# ESP32.net
KiCad netlist of a schematic drawn in Altium Designer
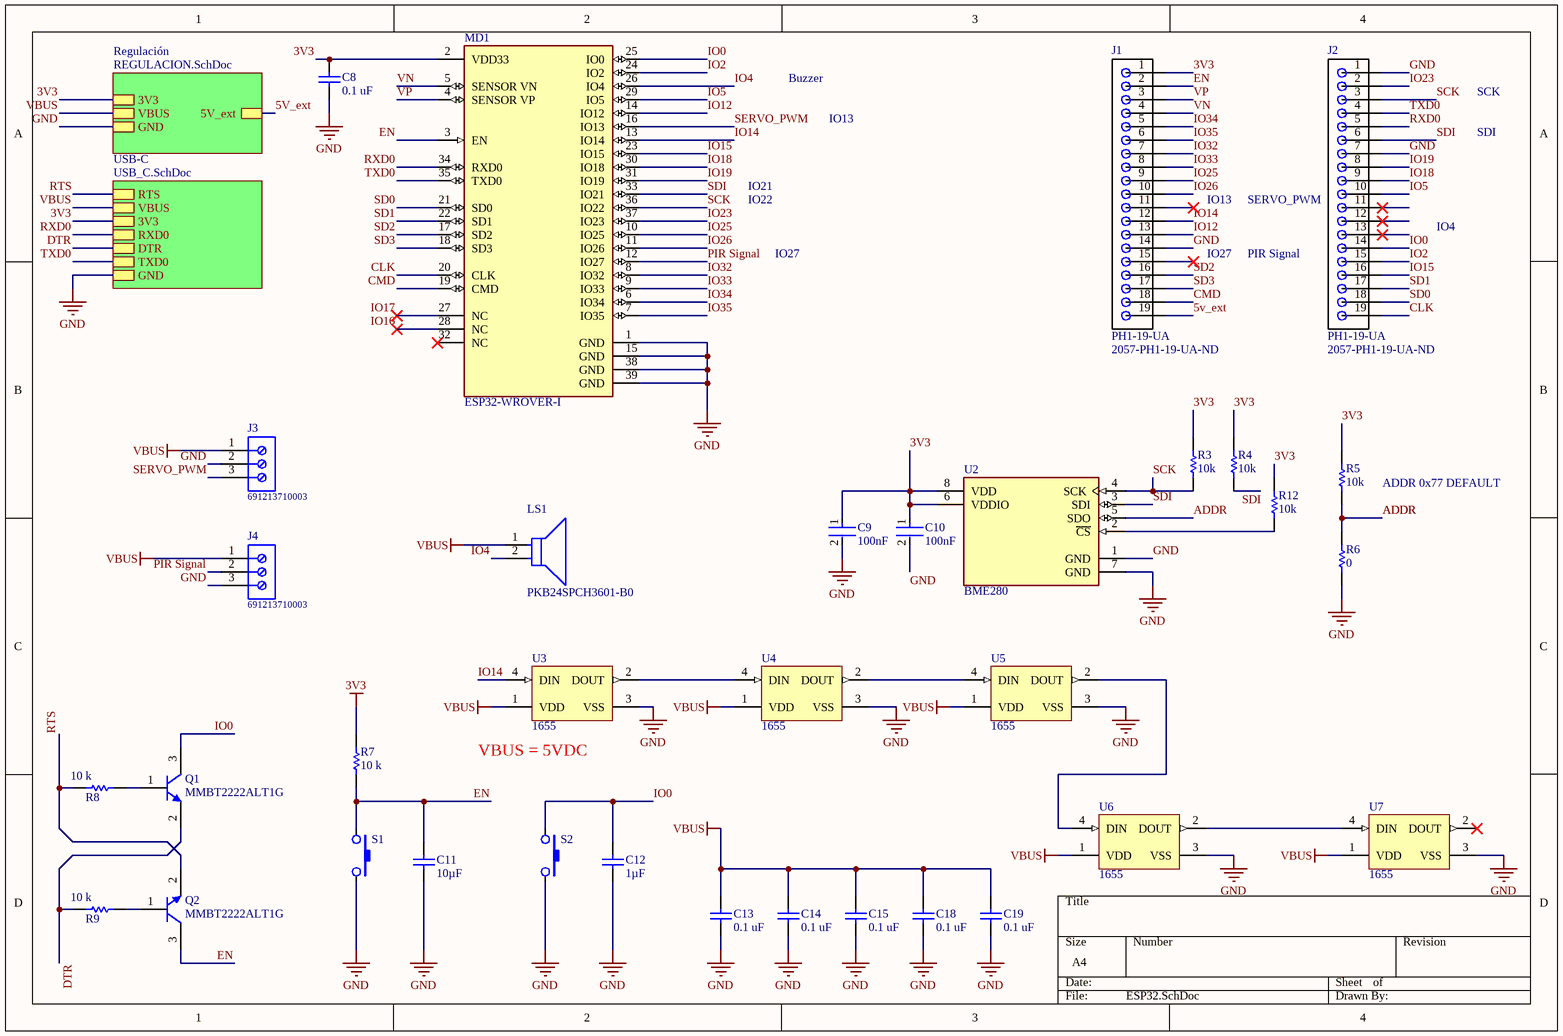
[diagram p0: ESP32.SchDoc]

(export (version "E")
  (design (tool "Eeschema 10.0.6"))
  (components
    (comp (ref "C8")
      (value "0.1 uF")
      (footprint "CAPC2013X94X50ML20T25")
      (description "Chip Capacitor, Ceramic, 0.1 uF, 10%, 50 V, 0805, RoHS, Tape and Reel")
      (fields (field (name "MANUFACTURER") "AVX"))
      (libsource (lib "Altium Content Vault") (part "CAP-NP-2"))
    )
    (comp (ref "C9")
      (value "100nF")
      (footprint "FP-C0805C-DN-MFG")
      (description "CAP CER 0.1UF 50V X7R 0805 C0805C104K5RACTU")
      (fields
        (field (name "MANUFACTURER PART NUMBER") "C0805C104K5RACTU")
        (field (name "MANUFACTURER") "KEMET")
      )
      (libsource (lib "Altium Content Vault") (part "b4654b650e69147ec39a6b967a45e02"))
    )
    (comp (ref "C10")
      (value "100nF")
      (footprint "FP-C0805C-DN-MFG")
      (description "CAP CER 0.1UF 50V X7R 0805 C0805C104K5RACTU")
      (fields
        (field (name "MANUFACTURER PART NUMBER") "C0805C104K5RACTU")
        (field (name "MANUFACTURER") "KEMET")
      )
      (libsource (lib "Altium Content Vault") (part "b4654b650e69147ec39a6b967a45e02"))
    )
    (comp (ref "C11")
      (value "10µF")
      (footprint "CAPC2013X145X50ML20T25")
      (description "1µF ±10% 16V Ceramic Capacitor X7R 0805 (2012 Metric)")
      (fields (field (name "MANUFACTURER") "Kemet") (field (name "PART NUMBER") "C0805C105K4RAC7800"))
      (libsource (lib "Altium Content Vault") (part "CAP"))
    )
    (comp (ref "C12")
      (value "1µF")
      (footprint "CAPC2013X145X50ML20T25")
      (description "1µF ±10% 16V Ceramic Capacitor X7R 0805 (2012 Metric)")
      (fields (field (name "MANUFACTURER") "Kemet") (field (name "PART NUMBER") "C0805C105K4RAC7800"))
      (libsource (lib "Altium Content Vault") (part "CAP"))
    )
    (comp (ref "C13")
      (value "0.1 uF")
      (footprint "CAPC2013X94X50ML20T25")
      (description "Chip Capacitor, Ceramic, 0.1 uF, 10%, 50 V, 0805, RoHS, Tape and Reel")
      (fields (field (name "MANUFACTURER") "AVX"))
      (libsource (lib "Altium Content Vault") (part "CAP-NP-2"))
    )
    (comp (ref "C14")
      (value "0.1 uF")
      (footprint "CAPC2013X94X50ML20T25")
      (description "Chip Capacitor, Ceramic, 0.1 uF, 10%, 50 V, 0805, RoHS, Tape and Reel")
      (fields (field (name "MANUFACTURER") "AVX"))
      (libsource (lib "Altium Content Vault") (part "CAP-NP-2"))
    )
    (comp (ref "C15")
      (value "0.1 uF")
      (footprint "CAPC2013X94X50ML20T25")
      (description "Chip Capacitor, Ceramic, 0.1 uF, 10%, 50 V, 0805, RoHS, Tape and Reel")
      (fields (field (name "MANUFACTURER") "AVX"))
      (libsource (lib "Altium Content Vault") (part "CAP-NP-2"))
    )
    (comp (ref "C18")
      (value "0.1 uF")
      (footprint "CAPC2013X94X50ML20T25")
      (description "Chip Capacitor, Ceramic, 0.1 uF, 10%, 50 V, 0805, RoHS, Tape and Reel")
      (fields (field (name "MANUFACTURER") "AVX"))
      (libsource (lib "Altium Content Vault") (part "CAP-NP-2"))
    )
    (comp (ref "C19")
      (value "0.1 uF")
      (footprint "CAPC2013X94X50ML20T25")
      (description "Chip Capacitor, Ceramic, 0.1 uF, 10%, 50 V, 0805, RoHS, Tape and Reel")
      (fields (field (name "MANUFACTURER") "AVX"))
      (libsource (lib "Altium Content Vault") (part "CAP-NP-2"))
    )
    (comp (ref "J1")
      (value "PH1-19-UA")
      (footprint "PH1-19-UA")
      (description "Connector Header Through Hole 19 position 0.100\" (2.54mm)")
      (fields (field (name "SUPPLIER PART NUMBER 1") "2057-PH1-19-UA-ND"))
      (libsource (lib "Isidro_Library") (part "PH1-19-UA"))
    )
    (comp (ref "J2")
      (value "PH1-19-UA")
      (footprint "PH1-19-UA")
      (description "Connector Header Through Hole 19 position 0.100\" (2.54mm)")
      (fields (field (name "SUPPLIER PART NUMBER 1") "2057-PH1-19-UA-ND"))
      (libsource (lib "Isidro_Library") (part "PH1-19-UA"))
    )
    (comp (ref "J3")
      (value "691213710003")
      (footprint "691213710003")
      (description "Serie 213 - 5.00 mm Horizontal Entry Modular with RisingCage Clamp WR-TBL, 3 pin")
      (fields (field (name "MANUFACTURER") "Wurth Elektronik") (field (name "PUBLISHER") "WurthElektronik"))
      (libsource (lib "Altium Content Vault") (part "WE-CN-1P-F-TB3"))
    )
    (comp (ref "J4")
      (value "691213710003")
      (footprint "691213710003")
      (description "Serie 213 - 5.00 mm Horizontal Entry Modular with RisingCage Clamp WR-TBL, 3 pin")
      (fields (field (name "MANUFACTURER") "Wurth Elektronik") (field (name "PUBLISHER") "WurthElektronik"))
      (libsource (lib "Altium Content Vault") (part "WE-CN-1P-F-TB3"))
    )
    (comp (ref "LS1")
      (value "PKB24SPCH3601-B0")
      (footprint "FP-PKB24SPCH3601-B0-MFG")
      (description "AUDIO PIEZO TRANSDUCER 3-15V TH")
      (libsource (lib "Altium Content Vault") (part "1973c4b650225fd2ddacaff6b763965"))
    )
    (comp (ref "MD1")
      (value "ESP32-WROVER-I")
      (footprint "FP-ESP32-WROVER-I-MFG")
      (description "SMD MODULE, ESP32-D0WDQ6, 32MBIT")
      (fields
        (field (name "MANUFACTURER") "Espressif")
        (field (name "OCTOPART") "https://octopart.com/esp32-wrover-i-espressif+systems-89171349")
      )
      (libsource (lib "Altium Content Vault") (part "cbbb37af8bcfe61dfd46ac9418f0340"))
    )
    (comp (ref "Q1")
      (value "MMBT2222ALT1G")
      (footprint "ONSC-SOT-23-3-318-08_V")
      (description "General Purpose Transistor, NPN Silicon, 3-Pin SOT-23, Pb-Free, Tape and Reel")
      (fields (field (name "MANUFACTURER") "On Semiconductor"))
      (libsource (lib "Altium Content Vault") (part "ONSC-NPN-B1E2C3-3"))
    )
    (comp (ref "Q2")
      (value "MMBT2222ALT1G")
      (footprint "ONSC-SOT-23-3-318-08_V")
      (description "General Purpose Transistor, NPN Silicon, 3-Pin SOT-23, Pb-Free, Tape and Reel")
      (fields (field (name "MANUFACTURER") "On Semiconductor"))
      (libsource (lib "Altium Content Vault") (part "ONSC-NPN-B1E2C3-3"))
    )
    (comp (ref "R3")
      (value "10k")
      (footprint "RESC2013X60X40LL20T25_A")
      (fields (field (name "TOLERANCE") "0.1%") (field (name "MANUFACTURER") "Panasonic"))
      (libsource (lib "Altium Content Vault") (part "RES-2"))
    )
    (comp (ref "R4")
      (value "10k")
      (footprint "RESC2013X60X40LL20T25_A")
      (fields (field (name "TOLERANCE") "0.1%") (field (name "MANUFACTURER") "Panasonic"))
      (libsource (lib "Altium Content Vault") (part "RES-2"))
    )
    (comp (ref "R5")
      (value "10k")
      (footprint "RESC2013X60X40LL20T25_A")
      (fields (field (name "TOLERANCE") "0.1%") (field (name "MANUFACTURER") "Panasonic"))
      (libsource (lib "Altium Content Vault") (part "RES-2"))
    )
    (comp (ref "R6")
      (value "0")
      (footprint "RESC2013X60X40LL20T25_A")
      (fields (field (name "TOLERANCE") "0.1%") (field (name "MANUFACTURER") "Panasonic"))
      (libsource (lib "Altium Content Vault") (part "RES-2"))
    )
    (comp (ref "R7")
      (value "10 k")
      (footprint "RESC2013X60X30ML20T20")
      (fields (field (name "PART NUMBER") "RK73B2ATTD103J") (field (name "MANUFACTURER") "KOA Speer"))
      (libsource (lib "Altium Content Vault") (part "RES"))
    )
    (comp (ref "R8")
      (value "10 k")
      (footprint "RESC2013X60X30ML20T20")
      (fields (field (name "PART NUMBER") "RK73B2ATTD103J") (field (name "MANUFACTURER") "KOA Speer"))
      (libsource (lib "Altium Content Vault") (part "RES"))
    )
    (comp (ref "R9")
      (value "10 k")
      (footprint "RESC2013X60X30ML20T20")
      (fields (field (name "PART NUMBER") "RK73B2ATTD103J") (field (name "MANUFACTURER") "KOA Speer"))
      (libsource (lib "Altium Content Vault") (part "RES"))
    )
    (comp (ref "R12")
      (value "10k")
      (footprint "RESC2013X60X40LL20T25_A")
      (fields (field (name "TOLERANCE") "0.1%") (field (name "MANUFACTURER") "Panasonic"))
      (libsource (lib "Altium Content Vault") (part "RES-2"))
    )
    (comp (ref "S1")
      (value "PTS820J25MSMTRLFS")
      (footprint "SMT_SW_PTS_820")
      (libsource (lib "SnapEDAsch") (part "PTS820J25MSMTRLFS"))
    )
    (comp (ref "S2")
      (value "IO0")
      (footprint "SMT_SW_PTS_820")
      (libsource (lib "SnapEDAsch") (part "PTS820J25MSMTRLFS"))
    )
    (comp (ref "U2")
      (value "BME280")
      (footprint "FP-BME280-MFG")
      (description "SENSOR PRESSURE HUMIDITY TEMP")
      (libsource (lib "Altium Content Vault") (part "d58e2f6669bc67e6a2bc6a28610ca79"))
    )
    (comp (ref "U3")
      (value "1655")
      (footprint "ADA-RGB-1655_V")
      (fields (field (name "MANUFACTURER") "Adafruit-Industries-LLC"))
      (libsource (lib "Altium Content Vault") (part "ADA-RGB-1655-4"))
    )
    (comp (ref "U4")
      (value "1655")
      (footprint "ADA-RGB-1655_V")
      (fields (field (name "MANUFACTURER") "Adafruit-Industries-LLC"))
      (libsource (lib "Altium Content Vault") (part "ADA-RGB-1655-4"))
    )
    (comp (ref "U5")
      (value "1655")
      (footprint "ADA-RGB-1655_V")
      (fields (field (name "MANUFACTURER") "Adafruit-Industries-LLC"))
      (libsource (lib "Altium Content Vault") (part "ADA-RGB-1655-4"))
    )
    (comp (ref "U6")
      (value "1655")
      (footprint "ADA-RGB-1655_V")
      (fields (field (name "MANUFACTURER") "Adafruit-Industries-LLC"))
      (libsource (lib "Altium Content Vault") (part "ADA-RGB-1655-4"))
    )
    (comp (ref "U7")
      (value "1655")
      (footprint "ADA-RGB-1655_V")
      (fields (field (name "MANUFACTURER") "Adafruit-Industries-LLC"))
      (libsource (lib "Altium Content Vault") (part "ADA-RGB-1655-4"))
    )
  )
  (nets
    (net (code "2") (name "/5v_ext") (class "Default")
      (node (ref "J1") (pin "19") (pinfunction "19_19") (pintype "passive"))
    )
    (net (code "3") (name "/ADDR") (class "Default")
      (node (ref "R5") (pin "1") (pinfunction "1_1") (pintype "passive"))
      (node (ref "R6") (pin "2") (pinfunction "2_2") (pintype "passive"))
      (node (ref "U2") (pin "5") (pinfunction "SDO_5") (pintype "bidirectional"))
    )
    (net (code "4") (name "/CLK") (class "Default")
      (node (ref "J2") (pin "19") (pinfunction "19_19") (pintype "passive"))
      (node (ref "MD1") (pin "20") (pinfunction "CLK_20") (pintype "bidirectional"))
    )
    (net (code "5") (name "/CMD") (class "Default")
      (node (ref "J1") (pin "18") (pinfunction "18_18") (pintype "passive"))
      (node (ref "MD1") (pin "19") (pinfunction "CMD_19") (pintype "bidirectional"))
    )
    (net (code "6") (name "/DTR") (class "Default")
      (node (ref "Q1") (pin "2") (pinfunction "E_2") (pintype "passive"))
      (node (ref "R9") (pin "2") (pinfunction "2_2") (pintype "passive"))
    )
    (net (code "7") (name "/EN") (class "Default")
      (node (ref "C11") (pin "2") (pinfunction "2_2") (pintype "passive"))
      (node (ref "J1") (pin "2") (pinfunction "2_2") (pintype "passive"))
      (node (ref "MD1") (pin "3") (pinfunction "EN_3") (pintype "input"))
      (node (ref "Q2") (pin "3") (pinfunction "C_3") (pintype "passive"))
      (node (ref "R7") (pin "1") (pinfunction "1_1") (pintype "passive"))
      (node (ref "S1") (pin "1") (pinfunction "1_1") (pintype "passive"))
    )
    (net (code "8") (name "/IO0") (class "Default")
      (node (ref "C12") (pin "2") (pinfunction "2_2") (pintype "passive"))
      (node (ref "J2") (pin "14") (pinfunction "14_14") (pintype "passive"))
      (node (ref "MD1") (pin "25") (pinfunction "IO0_25") (pintype "bidirectional"))
      (node (ref "Q1") (pin "3") (pinfunction "C_3") (pintype "passive"))
      (node (ref "S2") (pin "1") (pinfunction "1_1") (pintype "passive"))
    )
    (net (code "9") (name "/IO2") (class "Default")
      (node (ref "J2") (pin "15") (pinfunction "15_15") (pintype "passive"))
      (node (ref "MD1") (pin "24") (pinfunction "IO2_24") (pintype "bidirectional"))
    )
    (net (code "10") (name "/IO4") (class "Default")
      (node (ref "LS1") (pin "2") (pinfunction "A_2") (pintype "passive"))
      (node (ref "MD1") (pin "26") (pinfunction "IO4_26") (pintype "bidirectional"))
    )
    (net (code "11") (name "/IO5") (class "Default")
      (node (ref "J2") (pin "10") (pinfunction "10_10") (pintype "passive"))
      (node (ref "MD1") (pin "29") (pinfunction "IO5_29") (pintype "bidirectional"))
    )
    (net (code "12") (name "/IO12") (class "Default")
      (node (ref "J1") (pin "13") (pinfunction "13_13") (pintype "passive"))
      (node (ref "MD1") (pin "14") (pinfunction "IO12_14") (pintype "bidirectional"))
    )
    (net (code "13") (name "/IO14") (class "Default")
      (node (ref "J1") (pin "12") (pinfunction "12_12") (pintype "passive"))
      (node (ref "MD1") (pin "13") (pinfunction "IO14_13") (pintype "bidirectional"))
      (node (ref "U3") (pin "4") (pinfunction "DIN_4") (pintype "input"))
    )
    (net (code "14") (name "/IO15") (class "Default")
      (node (ref "J2") (pin "16") (pinfunction "16_16") (pintype "passive"))
      (node (ref "MD1") (pin "23") (pinfunction "IO15_23") (pintype "bidirectional"))
    )
    (net (code "15") (name "/IO16") (class "Default")
      (node (ref "MD1") (pin "28") (pinfunction "NC_28") (pintype "passive+no_connect"))
    )
    (net (code "16") (name "/IO17") (class "Default")
      (node (ref "MD1") (pin "27") (pinfunction "NC_27") (pintype "passive+no_connect"))
    )
    (net (code "17") (name "/IO18") (class "Default")
      (node (ref "J2") (pin "9") (pinfunction "9_9") (pintype "passive"))
      (node (ref "MD1") (pin "30") (pinfunction "IO18_30") (pintype "bidirectional"))
    )
    (net (code "18") (name "/IO19") (class "Default")
      (node (ref "J2") (pin "8") (pinfunction "8_8") (pintype "passive"))
      (node (ref "MD1") (pin "31") (pinfunction "IO19_31") (pintype "bidirectional"))
    )
    (net (code "19") (name "/IO23") (class "Default")
      (node (ref "J2") (pin "2") (pinfunction "2_2") (pintype "passive"))
      (node (ref "MD1") (pin "37") (pinfunction "IO23_37") (pintype "bidirectional"))
    )
    (net (code "20") (name "/IO25") (class "Default")
      (node (ref "J1") (pin "9") (pinfunction "9_9") (pintype "passive"))
      (node (ref "MD1") (pin "10") (pinfunction "IO25_10") (pintype "bidirectional"))
    )
    (net (code "21") (name "/IO26") (class "Default")
      (node (ref "J1") (pin "10") (pinfunction "10_10") (pintype "passive"))
      (node (ref "MD1") (pin "11") (pinfunction "IO26_11") (pintype "bidirectional"))
    )
    (net (code "22") (name "/IO32") (class "Default")
      (node (ref "J1") (pin "7") (pinfunction "7_7") (pintype "passive"))
      (node (ref "MD1") (pin "8") (pinfunction "IO32_8") (pintype "bidirectional"))
    )
    (net (code "23") (name "/IO33") (class "Default")
      (node (ref "J1") (pin "8") (pinfunction "8_8") (pintype "passive"))
      (node (ref "MD1") (pin "9") (pinfunction "IO33_9") (pintype "bidirectional"))
    )
    (net (code "24") (name "/IO34") (class "Default")
      (node (ref "J1") (pin "5") (pinfunction "5_5") (pintype "passive"))
      (node (ref "MD1") (pin "6") (pinfunction "IO34_6") (pintype "bidirectional"))
    )
    (net (code "25") (name "/IO35") (class "Default")
      (node (ref "J1") (pin "6") (pinfunction "6_6") (pintype "passive"))
      (node (ref "MD1") (pin "7") (pinfunction "IO35_7") (pintype "bidirectional"))
    )
    (net (code "26") (name "/PIR Signal") (class "Default")
      (node (ref "J4") (pin "2") (pinfunction "2_2") (pintype "passive"))
      (node (ref "MD1") (pin "12") (pinfunction "IO27_12") (pintype "bidirectional"))
    )
    (net (code "27") (name "/RTS") (class "Default")
      (node (ref "Q2") (pin "2") (pinfunction "E_2") (pintype "passive"))
      (node (ref "R8") (pin "2") (pinfunction "2_2") (pintype "passive"))
    )
    (net (code "28") (name "/RXD0") (class "Default")
      (node (ref "J2") (pin "5") (pinfunction "5_5") (pintype "passive"))
      (node (ref "MD1") (pin "34") (pinfunction "RXD0_34") (pintype "bidirectional"))
    )
    (net (code "29") (name "/SCK") (class "Default")
      (node (ref "J2") (pin "3") (pinfunction "3_3") (pintype "passive"))
      (node (ref "MD1") (pin "36") (pinfunction "IO22_36") (pintype "bidirectional"))
      (node (ref "R3") (pin "1") (pinfunction "1_1") (pintype "passive"))
      (node (ref "U2") (pin "4") (pinfunction "SCK_4") (pintype "input"))
    )
    (net (code "30") (name "/SD0") (class "Default")
      (node (ref "J2") (pin "18") (pinfunction "18_18") (pintype "passive"))
      (node (ref "MD1") (pin "21") (pinfunction "SD0_21") (pintype "bidirectional"))
    )
    (net (code "31") (name "/SD1") (class "Default")
      (node (ref "J2") (pin "17") (pinfunction "17_17") (pintype "passive"))
      (node (ref "MD1") (pin "22") (pinfunction "SD1_22") (pintype "bidirectional"))
    )
    (net (code "32") (name "/SD2") (class "Default")
      (node (ref "J1") (pin "16") (pinfunction "16_16") (pintype "passive"))
      (node (ref "MD1") (pin "17") (pinfunction "SD2_17") (pintype "bidirectional"))
    )
    (net (code "33") (name "/SD3") (class "Default")
      (node (ref "J1") (pin "17") (pinfunction "17_17") (pintype "passive"))
      (node (ref "MD1") (pin "18") (pinfunction "SD3_18") (pintype "bidirectional"))
    )
    (net (code "34") (name "/SDI") (class "Default")
      (node (ref "J2") (pin "6") (pinfunction "6_6") (pintype "passive"))
      (node (ref "MD1") (pin "33") (pinfunction "IO21_33") (pintype "bidirectional"))
      (node (ref "R4") (pin "1") (pinfunction "1_1") (pintype "passive"))
      (node (ref "U2") (pin "3") (pinfunction "SDI_3") (pintype "bidirectional"))
    )
    (net (code "35") (name "/SERVO_PWM") (class "Default")
      (node (ref "J3") (pin "3") (pinfunction "3_3") (pintype "passive"))
      (node (ref "MD1") (pin "16") (pinfunction "IO13_16") (pintype "bidirectional"))
    )
    (net (code "36") (name "/TXD0") (class "Default")
      (node (ref "J2") (pin "4") (pinfunction "4_4") (pintype "passive"))
      (node (ref "MD1") (pin "35") (pinfunction "TXD0_35") (pintype "bidirectional"))
    )
    (net (code "37") (name "/VN") (class "Default")
      (node (ref "J1") (pin "4") (pinfunction "4_4") (pintype "passive"))
      (node (ref "MD1") (pin "5") (pinfunction "SENSOR_VN_5") (pintype "bidirectional"))
    )
    (net (code "38") (name "/VP") (class "Default")
      (node (ref "J1") (pin "3") (pinfunction "3_3") (pintype "passive"))
      (node (ref "MD1") (pin "4") (pinfunction "SENSOR_VP_4") (pintype "bidirectional"))
    )
    (net (code "39") (name "3V3") (class "Default")
      (node (ref "C10") (pin "1") (pinfunction "1_1") (pintype "passive"))
      (node (ref "C8") (pin "2") (pinfunction "2_2") (pintype "passive"))
      (node (ref "C9") (pin "1") (pinfunction "1_1") (pintype "passive"))
      (node (ref "J1") (pin "1") (pinfunction "1_1") (pintype "passive"))
      (node (ref "MD1") (pin "2") (pinfunction "VDD33_2") (pintype "power_in"))
      (node (ref "R12") (pin "2") (pinfunction "2_2") (pintype "passive"))
      (node (ref "R3") (pin "2") (pinfunction "2_2") (pintype "passive"))
      (node (ref "R4") (pin "2") (pinfunction "2_2") (pintype "passive"))
      (node (ref "R5") (pin "2") (pinfunction "2_2") (pintype "passive"))
      (node (ref "R7") (pin "2") (pinfunction "2_2") (pintype "passive"))
      (node (ref "U2") (pin "6") (pinfunction "VDDIO_6") (pintype "power_in"))
      (node (ref "U2") (pin "8") (pinfunction "VDD_8") (pintype "power_in"))
    )
    (net (code "40") (name "GND") (class "Default")
      (node (ref "C10") (pin "2") (pinfunction "2_2") (pintype "passive"))
      (node (ref "C11") (pin "1") (pinfunction "1_1") (pintype "passive"))
      (node (ref "C12") (pin "1") (pinfunction "1_1") (pintype "passive"))
      (node (ref "C13") (pin "1") (pinfunction "1_1") (pintype "passive"))
      (node (ref "C14") (pin "1") (pinfunction "1_1") (pintype "passive"))
      (node (ref "C15") (pin "1") (pinfunction "1_1") (pintype "passive"))
      (node (ref "C18") (pin "1") (pinfunction "1_1") (pintype "passive"))
      (node (ref "C19") (pin "1") (pinfunction "1_1") (pintype "passive"))
      (node (ref "C8") (pin "1") (pinfunction "1_1") (pintype "passive"))
      (node (ref "C9") (pin "2") (pinfunction "2_2") (pintype "passive"))
      (node (ref "J1") (pin "14") (pinfunction "14_14") (pintype "passive"))
      (node (ref "J2") (pin "1") (pinfunction "1_1") (pintype "passive"))
      (node (ref "J2") (pin "7") (pinfunction "7_7") (pintype "passive"))
      (node (ref "J3") (pin "2") (pinfunction "2_2") (pintype "passive"))
      (node (ref "J4") (pin "3") (pinfunction "3_3") (pintype "passive"))
      (node (ref "MD1") (pin "1") (pinfunction "GND_1") (pintype "power_in"))
      (node (ref "MD1") (pin "15") (pinfunction "GND_15") (pintype "power_in"))
      (node (ref "MD1") (pin "38") (pinfunction "GND_38") (pintype "power_in"))
      (node (ref "MD1") (pin "39") (pinfunction "GND_39") (pintype "power_in"))
      (node (ref "R6") (pin "1") (pinfunction "1_1") (pintype "passive"))
      (node (ref "S1") (pin "2") (pinfunction "2_2") (pintype "passive"))
      (node (ref "S2") (pin "2") (pinfunction "2_2") (pintype "passive"))
      (node (ref "U2") (pin "1") (pinfunction "GND_1") (pintype "power_in"))
      (node (ref "U2") (pin "7") (pinfunction "GND_7") (pintype "power_in"))
      (node (ref "U3") (pin "3") (pinfunction "VSS_3") (pintype "power_in"))
      (node (ref "U4") (pin "3") (pinfunction "VSS_3") (pintype "power_in"))
      (node (ref "U5") (pin "3") (pinfunction "VSS_3") (pintype "power_in"))
      (node (ref "U6") (pin "3") (pinfunction "VSS_3") (pintype "power_in"))
      (node (ref "U7") (pin "3") (pinfunction "VSS_3") (pintype "power_in"))
    )
    (net (code "41") (name "Net-(Q1-B)") (class "Default")
      (node (ref "Q1") (pin "1") (pinfunction "B_1") (pintype "passive"))
      (node (ref "R8") (pin "1") (pinfunction "1_1") (pintype "passive"))
    )
    (net (code "42") (name "Net-(Q2-B)") (class "Default")
      (node (ref "Q2") (pin "1") (pinfunction "B_1") (pintype "passive"))
      (node (ref "R9") (pin "1") (pinfunction "1_1") (pintype "passive"))
    )
    (net (code "43") (name "Net-(U2-~{CS})") (class "Default")
      (node (ref "R12") (pin "1") (pinfunction "1_1") (pintype "passive"))
      (node (ref "U2") (pin "2") (pinfunction "~{CS}_2") (pintype "input"))
    )
    (net (code "44") (name "Net-(U3-DOUT)") (class "Default")
      (node (ref "U3") (pin "2") (pinfunction "DOUT_2") (pintype "output"))
      (node (ref "U4") (pin "4") (pinfunction "DIN_4") (pintype "input"))
    )
    (net (code "45") (name "Net-(U4-DOUT)") (class "Default")
      (node (ref "U4") (pin "2") (pinfunction "DOUT_2") (pintype "output"))
      (node (ref "U5") (pin "4") (pinfunction "DIN_4") (pintype "input"))
    )
    (net (code "46") (name "Net-(U5-DOUT)") (class "Default")
      (node (ref "U5") (pin "2") (pinfunction "DOUT_2") (pintype "output"))
      (node (ref "U6") (pin "4") (pinfunction "DIN_4") (pintype "input"))
    )
    (net (code "47") (name "Net-(U6-DOUT)") (class "Default")
      (node (ref "U6") (pin "2") (pinfunction "DOUT_2") (pintype "output"))
      (node (ref "U7") (pin "4") (pinfunction "DIN_4") (pintype "input"))
    )
    (net (code "48") (name "VBUS") (class "Default")
      (node (ref "C13") (pin "2") (pinfunction "2_2") (pintype "passive"))
      (node (ref "C14") (pin "2") (pinfunction "2_2") (pintype "passive"))
      (node (ref "C15") (pin "2") (pinfunction "2_2") (pintype "passive"))
      (node (ref "C18") (pin "2") (pinfunction "2_2") (pintype "passive"))
      (node (ref "C19") (pin "2") (pinfunction "2_2") (pintype "passive"))
      (node (ref "J3") (pin "1") (pinfunction "1_1") (pintype "passive"))
      (node (ref "J4") (pin "1") (pinfunction "1_1") (pintype "passive"))
      (node (ref "LS1") (pin "1") (pinfunction "C_1") (pintype "passive"))
      (node (ref "U3") (pin "1") (pinfunction "VDD_1") (pintype "power_in"))
      (node (ref "U4") (pin "1") (pinfunction "VDD_1") (pintype "power_in"))
      (node (ref "U5") (pin "1") (pinfunction "VDD_1") (pintype "power_in"))
      (node (ref "U6") (pin "1") (pinfunction "VDD_1") (pintype "power_in"))
      (node (ref "U7") (pin "1") (pinfunction "VDD_1") (pintype "power_in"))
    )
    (net (code "49") (name "unconnected-(J1-Pad11)") (class "Default")
      (node (ref "J1") (pin "11") (pinfunction "11_11") (pintype "passive+no_connect"))
    )
    (net (code "50") (name "unconnected-(J1-Pad15)") (class "Default")
      (node (ref "J1") (pin "15") (pinfunction "15_15") (pintype "passive+no_connect"))
    )
    (net (code "51") (name "unconnected-(J2-Pad11)") (class "Default")
      (node (ref "J2") (pin "11") (pinfunction "11_11") (pintype "passive+no_connect"))
    )
    (net (code "52") (name "unconnected-(J2-Pad12)") (class "Default")
      (node (ref "J2") (pin "12") (pinfunction "12_12") (pintype "passive+no_connect"))
    )
    (net (code "53") (name "unconnected-(J2-Pad13)") (class "Default")
      (node (ref "J2") (pin "13") (pinfunction "13_13") (pintype "passive+no_connect"))
    )
    (net (code "54") (name "unconnected-(MD1-NC-Pad32)") (class "Default")
      (node (ref "MD1") (pin "32") (pinfunction "NC_32") (pintype "passive+no_connect"))
    )
    (net (code "55") (name "unconnected-(U7-DOUT-Pad2)") (class "Default")
      (node (ref "U7") (pin "2") (pinfunction "DOUT_2") (pintype "output+no_connect"))
    )
  )
)
